# MEMC_FFC.net
KiCad netlist of a schematic drawn in Altium Designer
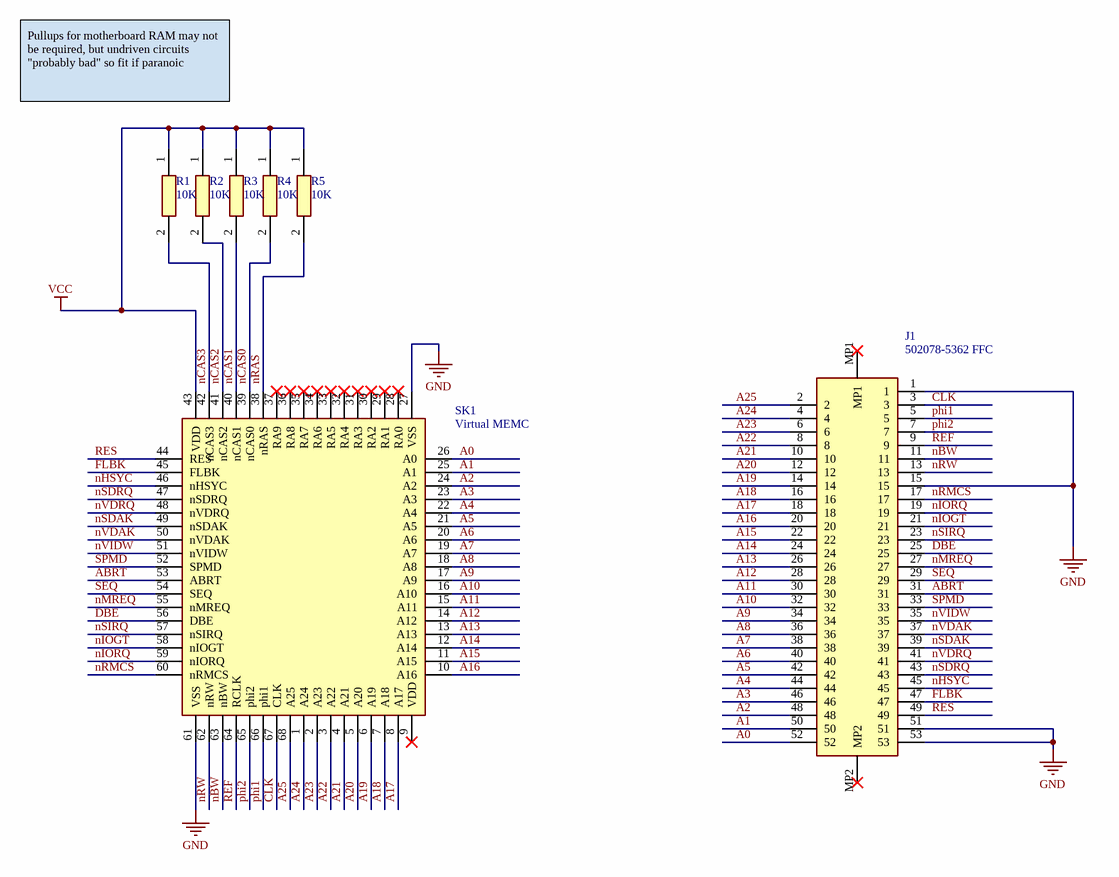
[diagram p0: MEMC_FFC.SchDoc]

(export (version "E")
  (design (tool "Eeschema 10.0.6"))
  (components
    (comp (ref "J1")
      (value "502078-5362 FFC")
      (footprint "SamacSys:5020785362")
      (description "Connector")
      (fields
        (field (name "MANUFACTURER_PART_NUMBER") "502078-5362")
        (field (name "MOUSER PART NUMBER") "538-502078-5362")
      )
      (libsource (lib "*") (part "502078-5362"))
    )
    (comp (ref "R1")
      (value "10K")
      (footprint "SamacSys:RESC1005X40N")
      (description "Resistor")
      (fields
        (field (name "MANUFACTURER_PART_NUMBER") "CRCW040210K0FKEDHP")
        (field (name "MOUSER PART NUMBER") "71-CRCW040210K0FKEDH")
      )
      (libsource (lib "*") (part "CRCW040210K0FKEDHP"))
    )
    (comp (ref "R2")
      (value "10K")
      (footprint "SamacSys:RESC1005X40N")
      (description "Resistor")
      (fields
        (field (name "MANUFACTURER_PART_NUMBER") "CRCW040210K0FKEDHP")
        (field (name "MOUSER PART NUMBER") "71-CRCW040210K0FKEDH")
      )
      (libsource (lib "*") (part "CRCW040210K0FKEDHP"))
    )
    (comp (ref "R3")
      (value "10K")
      (footprint "SamacSys:RESC1005X40N")
      (description "Resistor")
      (fields
        (field (name "MANUFACTURER_PART_NUMBER") "CRCW040210K0FKEDHP")
        (field (name "MOUSER PART NUMBER") "71-CRCW040210K0FKEDH")
      )
      (libsource (lib "*") (part "CRCW040210K0FKEDHP"))
    )
    (comp (ref "R4")
      (value "10K")
      (footprint "SamacSys:RESC1005X40N")
      (description "Resistor")
      (fields
        (field (name "MANUFACTURER_PART_NUMBER") "CRCW040210K0FKEDHP")
        (field (name "MOUSER PART NUMBER") "71-CRCW040210K0FKEDH")
      )
      (libsource (lib "*") (part "CRCW040210K0FKEDHP"))
    )
    (comp (ref "R5")
      (value "10K")
      (footprint "SamacSys:RESC1005X40N")
      (description "Resistor")
      (fields
        (field (name "MANUFACTURER_PART_NUMBER") "CRCW040210K0FKEDHP")
        (field (name "MOUSER PART NUMBER") "71-CRCW040210K0FKEDH")
      )
      (libsource (lib "*") (part "CRCW040210K0FKEDHP"))
    )
    (comp (ref "SK1")
      (value "Virtual MEMC")
      (footprint "SamacSys:846821B1RKTR")
      (description "MEMC socket")
      (fields
        (field (name "MANUFACTURER_PART_NUMBER") "8468-21B1-RK-TR")
        (field (name "MOUSER PART NUMBER") "517-8468-21B1-RK-TR")
      )
      (libsource (lib "Acorn") (part "MEMC_Skt"))
    )
  )
  (nets
    (net (code "1") (name "/A0") (class "Default")
      (node (ref "J1") (pin "52") (pinfunction "52_52") (pintype "passive"))
      (node (ref "SK1") (pin "26") (pinfunction "A0_26") (pintype "passive"))
    )
    (net (code "2") (name "/A1") (class "Default")
      (node (ref "J1") (pin "50") (pinfunction "50_50") (pintype "passive"))
      (node (ref "SK1") (pin "25") (pinfunction "A1_25") (pintype "passive"))
    )
    (net (code "3") (name "/A2") (class "Default")
      (node (ref "J1") (pin "48") (pinfunction "48_48") (pintype "passive"))
      (node (ref "SK1") (pin "24") (pinfunction "A2_24") (pintype "passive"))
    )
    (net (code "4") (name "/A3") (class "Default")
      (node (ref "J1") (pin "46") (pinfunction "46_46") (pintype "passive"))
      (node (ref "SK1") (pin "23") (pinfunction "A3_23") (pintype "passive"))
    )
    (net (code "5") (name "/A4") (class "Default")
      (node (ref "J1") (pin "44") (pinfunction "44_44") (pintype "passive"))
      (node (ref "SK1") (pin "22") (pinfunction "A4_22") (pintype "passive"))
    )
    (net (code "6") (name "/A5") (class "Default")
      (node (ref "J1") (pin "42") (pinfunction "42_42") (pintype "passive"))
      (node (ref "SK1") (pin "21") (pinfunction "A5_21") (pintype "passive"))
    )
    (net (code "7") (name "/A6") (class "Default")
      (node (ref "J1") (pin "40") (pinfunction "40_40") (pintype "passive"))
      (node (ref "SK1") (pin "20") (pinfunction "A6_20") (pintype "passive"))
    )
    (net (code "8") (name "/A7") (class "Default")
      (node (ref "J1") (pin "38") (pinfunction "38_38") (pintype "passive"))
      (node (ref "SK1") (pin "19") (pinfunction "A7_19") (pintype "passive"))
    )
    (net (code "9") (name "/A8") (class "Default")
      (node (ref "J1") (pin "36") (pinfunction "36_36") (pintype "passive"))
      (node (ref "SK1") (pin "18") (pinfunction "A8_18") (pintype "passive"))
    )
    (net (code "10") (name "/A9") (class "Default")
      (node (ref "J1") (pin "34") (pinfunction "34_34") (pintype "passive"))
      (node (ref "SK1") (pin "17") (pinfunction "A9_17") (pintype "passive"))
    )
    (net (code "11") (name "/A10") (class "Default")
      (node (ref "J1") (pin "32") (pinfunction "32_32") (pintype "passive"))
      (node (ref "SK1") (pin "16") (pinfunction "A10_16") (pintype "passive"))
    )
    (net (code "12") (name "/A11") (class "Default")
      (node (ref "J1") (pin "30") (pinfunction "30_30") (pintype "passive"))
      (node (ref "SK1") (pin "15") (pinfunction "A11_15") (pintype "passive"))
    )
    (net (code "13") (name "/A12") (class "Default")
      (node (ref "J1") (pin "28") (pinfunction "28_28") (pintype "passive"))
      (node (ref "SK1") (pin "14") (pinfunction "A12_14") (pintype "passive"))
    )
    (net (code "14") (name "/A13") (class "Default")
      (node (ref "J1") (pin "26") (pinfunction "26_26") (pintype "passive"))
      (node (ref "SK1") (pin "13") (pinfunction "A13_13") (pintype "passive"))
    )
    (net (code "15") (name "/A14") (class "Default")
      (node (ref "J1") (pin "24") (pinfunction "24_24") (pintype "passive"))
      (node (ref "SK1") (pin "12") (pinfunction "A14_12") (pintype "passive"))
    )
    (net (code "16") (name "/A15") (class "Default")
      (node (ref "J1") (pin "22") (pinfunction "22_22") (pintype "passive"))
      (node (ref "SK1") (pin "11") (pinfunction "A15_11") (pintype "passive"))
    )
    (net (code "17") (name "/A16") (class "Default")
      (node (ref "J1") (pin "20") (pinfunction "20_20") (pintype "passive"))
      (node (ref "SK1") (pin "10") (pinfunction "A16_10") (pintype "passive"))
    )
    (net (code "18") (name "/A17") (class "Default")
      (node (ref "J1") (pin "18") (pinfunction "18_18") (pintype "passive"))
      (node (ref "SK1") (pin "8") (pinfunction "A17_8") (pintype "passive"))
    )
    (net (code "19") (name "/A18") (class "Default")
      (node (ref "J1") (pin "16") (pinfunction "16_16") (pintype "passive"))
      (node (ref "SK1") (pin "7") (pinfunction "A18_7") (pintype "passive"))
    )
    (net (code "20") (name "/A19") (class "Default")
      (node (ref "J1") (pin "14") (pinfunction "14_14") (pintype "passive"))
      (node (ref "SK1") (pin "6") (pinfunction "A19_6") (pintype "passive"))
    )
    (net (code "21") (name "/A20") (class "Default")
      (node (ref "J1") (pin "12") (pinfunction "12_12") (pintype "passive"))
      (node (ref "SK1") (pin "5") (pinfunction "A20_5") (pintype "passive"))
    )
    (net (code "22") (name "/A21") (class "Default")
      (node (ref "J1") (pin "10") (pinfunction "10_10") (pintype "passive"))
      (node (ref "SK1") (pin "4") (pinfunction "A21_4") (pintype "passive"))
    )
    (net (code "23") (name "/A22") (class "Default")
      (node (ref "J1") (pin "8") (pinfunction "8_8") (pintype "passive"))
      (node (ref "SK1") (pin "3") (pinfunction "A22_3") (pintype "passive"))
    )
    (net (code "24") (name "/A23") (class "Default")
      (node (ref "J1") (pin "6") (pinfunction "6_6") (pintype "passive"))
      (node (ref "SK1") (pin "2") (pinfunction "A23_2") (pintype "passive"))
    )
    (net (code "25") (name "/A24") (class "Default")
      (node (ref "J1") (pin "4") (pinfunction "4_4") (pintype "passive"))
      (node (ref "SK1") (pin "1") (pinfunction "A24_1") (pintype "passive"))
    )
    (net (code "26") (name "/A25") (class "Default")
      (node (ref "J1") (pin "2") (pinfunction "2_2") (pintype "passive"))
      (node (ref "SK1") (pin "68") (pinfunction "A25_68") (pintype "passive"))
    )
    (net (code "27") (name "/ABRT") (class "Default")
      (node (ref "J1") (pin "31") (pinfunction "31_31") (pintype "passive"))
      (node (ref "SK1") (pin "53") (pinfunction "ABRT_53") (pintype "passive"))
    )
    (net (code "28") (name "/CLK") (class "Default")
      (node (ref "J1") (pin "3") (pinfunction "3_3") (pintype "passive"))
      (node (ref "SK1") (pin "67") (pinfunction "CLK_67") (pintype "passive"))
    )
    (net (code "29") (name "/DBE") (class "Default")
      (node (ref "J1") (pin "25") (pinfunction "25_25") (pintype "passive"))
      (node (ref "SK1") (pin "56") (pinfunction "DBE_56") (pintype "passive"))
    )
    (net (code "30") (name "/FLBK") (class "Default")
      (node (ref "J1") (pin "47") (pinfunction "47_47") (pintype "passive"))
      (node (ref "SK1") (pin "45") (pinfunction "FLBK_45") (pintype "passive"))
    )
    (net (code "31") (name "/REF") (class "Default")
      (node (ref "J1") (pin "9") (pinfunction "9_9") (pintype "passive"))
      (node (ref "SK1") (pin "64") (pinfunction "RCLK_64") (pintype "passive"))
    )
    (net (code "32") (name "/RES") (class "Default")
      (node (ref "J1") (pin "49") (pinfunction "49_49") (pintype "passive"))
      (node (ref "SK1") (pin "44") (pinfunction "RES_44") (pintype "passive"))
    )
    (net (code "33") (name "/SEQ") (class "Default")
      (node (ref "J1") (pin "29") (pinfunction "29_29") (pintype "passive"))
      (node (ref "SK1") (pin "54") (pinfunction "SEQ_54") (pintype "passive"))
    )
    (net (code "34") (name "/SPMD") (class "Default")
      (node (ref "J1") (pin "33") (pinfunction "33_33") (pintype "passive"))
      (node (ref "SK1") (pin "52") (pinfunction "SPMD_52") (pintype "passive"))
    )
    (net (code "35") (name "/nBW") (class "Default")
      (node (ref "J1") (pin "11") (pinfunction "11_11") (pintype "passive"))
      (node (ref "SK1") (pin "63") (pinfunction "nBW_63") (pintype "passive"))
    )
    (net (code "36") (name "/nCAS0") (class "Default")
      (node (ref "R4") (pin "2") (pinfunction "2_2") (pintype "passive"))
      (node (ref "SK1") (pin "39") (pinfunction "nCAS0_39") (pintype "passive"))
    )
    (net (code "37") (name "/nCAS1") (class "Default")
      (node (ref "R3") (pin "2") (pinfunction "2_2") (pintype "passive"))
      (node (ref "SK1") (pin "40") (pinfunction "nCAS1_40") (pintype "passive"))
    )
    (net (code "38") (name "/nCAS2") (class "Default")
      (node (ref "R2") (pin "2") (pinfunction "2_2") (pintype "passive"))
      (node (ref "SK1") (pin "41") (pinfunction "nCAS2_41") (pintype "passive"))
    )
    (net (code "39") (name "/nCAS3") (class "Default")
      (node (ref "R1") (pin "2") (pinfunction "2_2") (pintype "passive"))
      (node (ref "SK1") (pin "42") (pinfunction "nCAS3_42") (pintype "passive"))
    )
    (net (code "40") (name "/nHSYC") (class "Default")
      (node (ref "J1") (pin "45") (pinfunction "45_45") (pintype "passive"))
      (node (ref "SK1") (pin "46") (pinfunction "nHSYC_46") (pintype "passive"))
    )
    (net (code "41") (name "/nIOGT") (class "Default")
      (node (ref "J1") (pin "21") (pinfunction "21_21") (pintype "passive"))
      (node (ref "SK1") (pin "58") (pinfunction "nIOGT_58") (pintype "passive"))
    )
    (net (code "42") (name "/nIORQ") (class "Default")
      (node (ref "J1") (pin "19") (pinfunction "19_19") (pintype "passive"))
      (node (ref "SK1") (pin "59") (pinfunction "nIORQ_59") (pintype "passive"))
    )
    (net (code "43") (name "/nMREQ") (class "Default")
      (node (ref "J1") (pin "27") (pinfunction "27_27") (pintype "passive"))
      (node (ref "SK1") (pin "55") (pinfunction "nMREQ_55") (pintype "passive"))
    )
    (net (code "44") (name "/nRAS") (class "Default")
      (node (ref "R5") (pin "2") (pinfunction "2_2") (pintype "passive"))
      (node (ref "SK1") (pin "38") (pinfunction "nRAS_38") (pintype "passive"))
    )
    (net (code "45") (name "/nRMCS") (class "Default")
      (node (ref "J1") (pin "17") (pinfunction "17_17") (pintype "passive"))
      (node (ref "SK1") (pin "60") (pinfunction "nRMCS_60") (pintype "passive"))
    )
    (net (code "46") (name "/nRW") (class "Default")
      (node (ref "J1") (pin "13") (pinfunction "13_13") (pintype "passive"))
      (node (ref "SK1") (pin "62") (pinfunction "nRW_62") (pintype "passive"))
    )
    (net (code "47") (name "/nSDAK") (class "Default")
      (node (ref "J1") (pin "39") (pinfunction "39_39") (pintype "passive"))
      (node (ref "SK1") (pin "49") (pinfunction "nSDAK_49") (pintype "passive"))
    )
    (net (code "48") (name "/nSDRQ") (class "Default")
      (node (ref "J1") (pin "43") (pinfunction "43_43") (pintype "passive"))
      (node (ref "SK1") (pin "47") (pinfunction "nSDRQ_47") (pintype "passive"))
    )
    (net (code "49") (name "/nSIRQ") (class "Default")
      (node (ref "J1") (pin "23") (pinfunction "23_23") (pintype "passive"))
      (node (ref "SK1") (pin "57") (pinfunction "nSIRQ_57") (pintype "passive"))
    )
    (net (code "50") (name "/nVDAK") (class "Default")
      (node (ref "J1") (pin "37") (pinfunction "37_37") (pintype "passive"))
      (node (ref "SK1") (pin "50") (pinfunction "nVDAK_50") (pintype "passive"))
    )
    (net (code "51") (name "/nVDRQ") (class "Default")
      (node (ref "J1") (pin "41") (pinfunction "41_41") (pintype "passive"))
      (node (ref "SK1") (pin "48") (pinfunction "nVDRQ_48") (pintype "passive"))
    )
    (net (code "52") (name "/nVIDW") (class "Default")
      (node (ref "J1") (pin "35") (pinfunction "35_35") (pintype "passive"))
      (node (ref "SK1") (pin "51") (pinfunction "nVIDW_51") (pintype "passive"))
    )
    (net (code "53") (name "/phi1") (class "Default")
      (node (ref "J1") (pin "5") (pinfunction "5_5") (pintype "passive"))
      (node (ref "SK1") (pin "66") (pinfunction "phi1_66") (pintype "passive"))
    )
    (net (code "54") (name "/phi2") (class "Default")
      (node (ref "J1") (pin "7") (pinfunction "7_7") (pintype "passive"))
      (node (ref "SK1") (pin "65") (pinfunction "phi2_65") (pintype "passive"))
    )
    (net (code "55") (name "GND") (class "Default")
      (node (ref "J1") (pin "1") (pinfunction "1_1") (pintype "passive"))
      (node (ref "J1") (pin "15") (pinfunction "15_15") (pintype "passive"))
      (node (ref "J1") (pin "51") (pinfunction "51_51") (pintype "passive"))
      (node (ref "J1") (pin "53") (pinfunction "53_53") (pintype "passive"))
      (node (ref "SK1") (pin "27") (pinfunction "VSS_27") (pintype "passive"))
      (node (ref "SK1") (pin "61") (pinfunction "VSS_61") (pintype "passive"))
    )
    (net (code "56") (name "VCC") (class "Default")
      (node (ref "R1") (pin "1") (pinfunction "1_1") (pintype "passive"))
      (node (ref "R2") (pin "1") (pinfunction "1_1") (pintype "passive"))
      (node (ref "R3") (pin "1") (pinfunction "1_1") (pintype "passive"))
      (node (ref "R4") (pin "1") (pinfunction "1_1") (pintype "passive"))
      (node (ref "R5") (pin "1") (pinfunction "1_1") (pintype "passive"))
      (node (ref "SK1") (pin "43") (pinfunction "VDD_43") (pintype "passive"))
    )
    (net (code "57") (name "unconnected-(J1-PadMP1)") (class "Default")
      (node (ref "J1") (pin "MP1") (pinfunction "MP1_MP1") (pintype "passive+no_connect"))
    )
    (net (code "58") (name "unconnected-(J1-PadMP2)") (class "Default")
      (node (ref "J1") (pin "MP2") (pinfunction "MP2_MP2") (pintype "passive+no_connect"))
    )
    (net (code "59") (name "unconnected-(SK1-RA0-Pad28)") (class "Default")
      (node (ref "SK1") (pin "28") (pinfunction "RA0_28") (pintype "passive+no_connect"))
    )
    (net (code "60") (name "unconnected-(SK1-RA1-Pad29)") (class "Default")
      (node (ref "SK1") (pin "29") (pinfunction "RA1_29") (pintype "passive+no_connect"))
    )
    (net (code "61") (name "unconnected-(SK1-RA2-Pad30)") (class "Default")
      (node (ref "SK1") (pin "30") (pinfunction "RA2_30") (pintype "passive+no_connect"))
    )
    (net (code "62") (name "unconnected-(SK1-RA3-Pad31)") (class "Default")
      (node (ref "SK1") (pin "31") (pinfunction "RA3_31") (pintype "passive+no_connect"))
    )
    (net (code "63") (name "unconnected-(SK1-RA4-Pad32)") (class "Default")
      (node (ref "SK1") (pin "32") (pinfunction "RA4_32") (pintype "passive+no_connect"))
    )
    (net (code "64") (name "unconnected-(SK1-RA5-Pad33)") (class "Default")
      (node (ref "SK1") (pin "33") (pinfunction "RA5_33") (pintype "passive+no_connect"))
    )
    (net (code "65") (name "unconnected-(SK1-RA6-Pad34)") (class "Default")
      (node (ref "SK1") (pin "34") (pinfunction "RA6_34") (pintype "passive+no_connect"))
    )
    (net (code "66") (name "unconnected-(SK1-RA7-Pad35)") (class "Default")
      (node (ref "SK1") (pin "35") (pinfunction "RA7_35") (pintype "passive+no_connect"))
    )
    (net (code "67") (name "unconnected-(SK1-RA8-Pad36)") (class "Default")
      (node (ref "SK1") (pin "36") (pinfunction "RA8_36") (pintype "passive+no_connect"))
    )
    (net (code "68") (name "unconnected-(SK1-RA9-Pad37)") (class "Default")
      (node (ref "SK1") (pin "37") (pinfunction "RA9_37") (pintype "passive+no_connect"))
    )
    (net (code "69") (name "unconnected-(SK1-VDD-Pad9)") (class "Default")
      (node (ref "SK1") (pin "9") (pinfunction "VDD_9") (pintype "passive+no_connect"))
    )
  )
)
